# LIMIT_SWITCH.net
KiCad netlist of a schematic drawn in Altium Designer
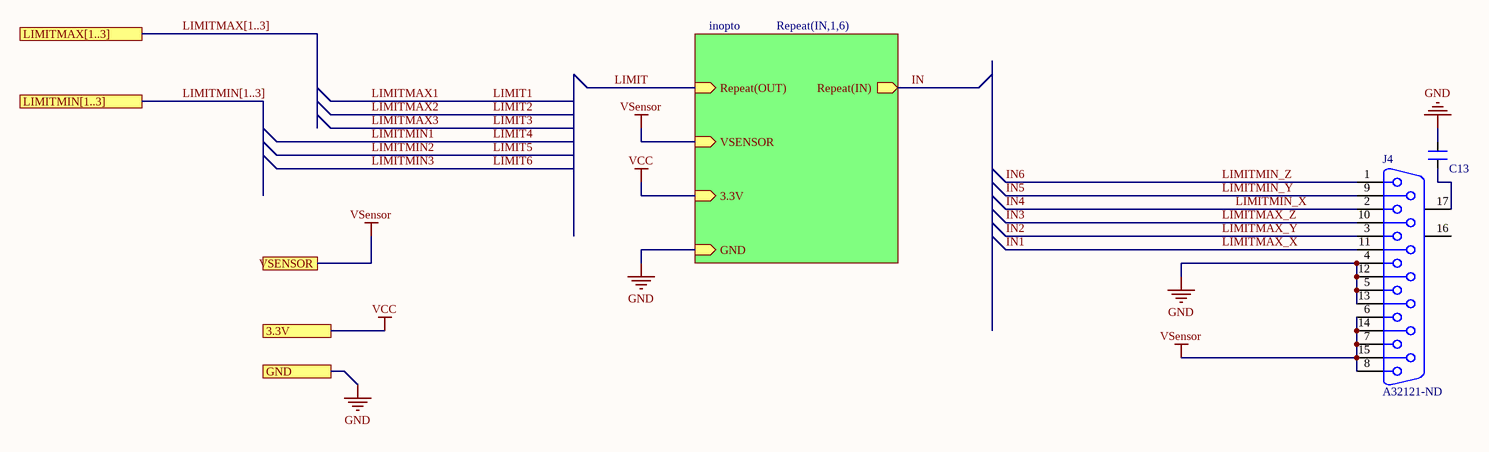
[diagram p0: LIMIT SWITCH.SchDoc]

(export (version "E")
  (design (tool "Eeschema 10.0.6"))
  (components
    (comp (ref "C13") (value "CN") (footprint "CN-SMD-0603_big") (libsource (lib "nhan") (part "CN")))
    (comp (ref "J4")
      (value "A32121-ND")
      (footprint "DB15")
      (description "Receptacle Assembly, 15 Position, Right Angle")
      (fields (field (name "PUBLISHER") "Altium Limited"))
      (libsource (lib "nhan") (part "DB15"))
    )
  )
  (nets
    (net (code "2") (name "/IN1") (class "Default")
      (node (ref "J4") (pin "11") (pinfunction "11_11") (pintype "passive"))
    )
    (net (code "3") (name "/IN2") (class "Default")
      (node (ref "J4") (pin "3") (pinfunction "3_3") (pintype "passive"))
    )
    (net (code "4") (name "/IN3") (class "Default")
      (node (ref "J4") (pin "10") (pinfunction "10_10") (pintype "passive"))
    )
    (net (code "5") (name "/IN4") (class "Default")
      (node (ref "J4") (pin "2") (pinfunction "2_2") (pintype "passive"))
    )
    (net (code "6") (name "/IN5") (class "Default")
      (node (ref "J4") (pin "9") (pinfunction "9_9") (pintype "passive"))
    )
    (net (code "7") (name "/IN6") (class "Default")
      (node (ref "J4") (pin "1") (pinfunction "1_1") (pintype "passive"))
    )
    (net (code "17") (name "GND") (class "Default")
      (node (ref "C13") (pin "2") (pinfunction "2_2") (pintype "passive"))
      (node (ref "J4") (pin "12") (pinfunction "12_12") (pintype "passive"))
      (node (ref "J4") (pin "13") (pinfunction "13_13") (pintype "passive"))
      (node (ref "J4") (pin "4") (pinfunction "4_4") (pintype "passive"))
      (node (ref "J4") (pin "5") (pinfunction "5_5") (pintype "passive"))
    )
    (net (code "18") (name "Net-(J4-MH2)") (class "Default")
      (node (ref "C13") (pin "1") (pinfunction "1_1") (pintype "passive"))
      (node (ref "J4") (pin "17") (pinfunction "MH2_17") (pintype "passive"))
    )
    (net (code "20") (name "VSensor") (class "Default")
      (node (ref "J4") (pin "14") (pinfunction "14_14") (pintype "passive"))
      (node (ref "J4") (pin "15") (pinfunction "15_15") (pintype "passive"))
      (node (ref "J4") (pin "6") (pinfunction "6_6") (pintype "passive"))
      (node (ref "J4") (pin "7") (pinfunction "7_7") (pintype "passive"))
      (node (ref "J4") (pin "8") (pinfunction "8_8") (pintype "passive"))
    )
    (net (code "21") (name "unconnected-(J4-MH1-Pad16)") (class "Default")
      (node (ref "J4") (pin "16") (pinfunction "MH1_16") (pintype "passive"))
    )
  )
)
